# breakout.net
KiCad netlist of a schematic drawn in EAGLE
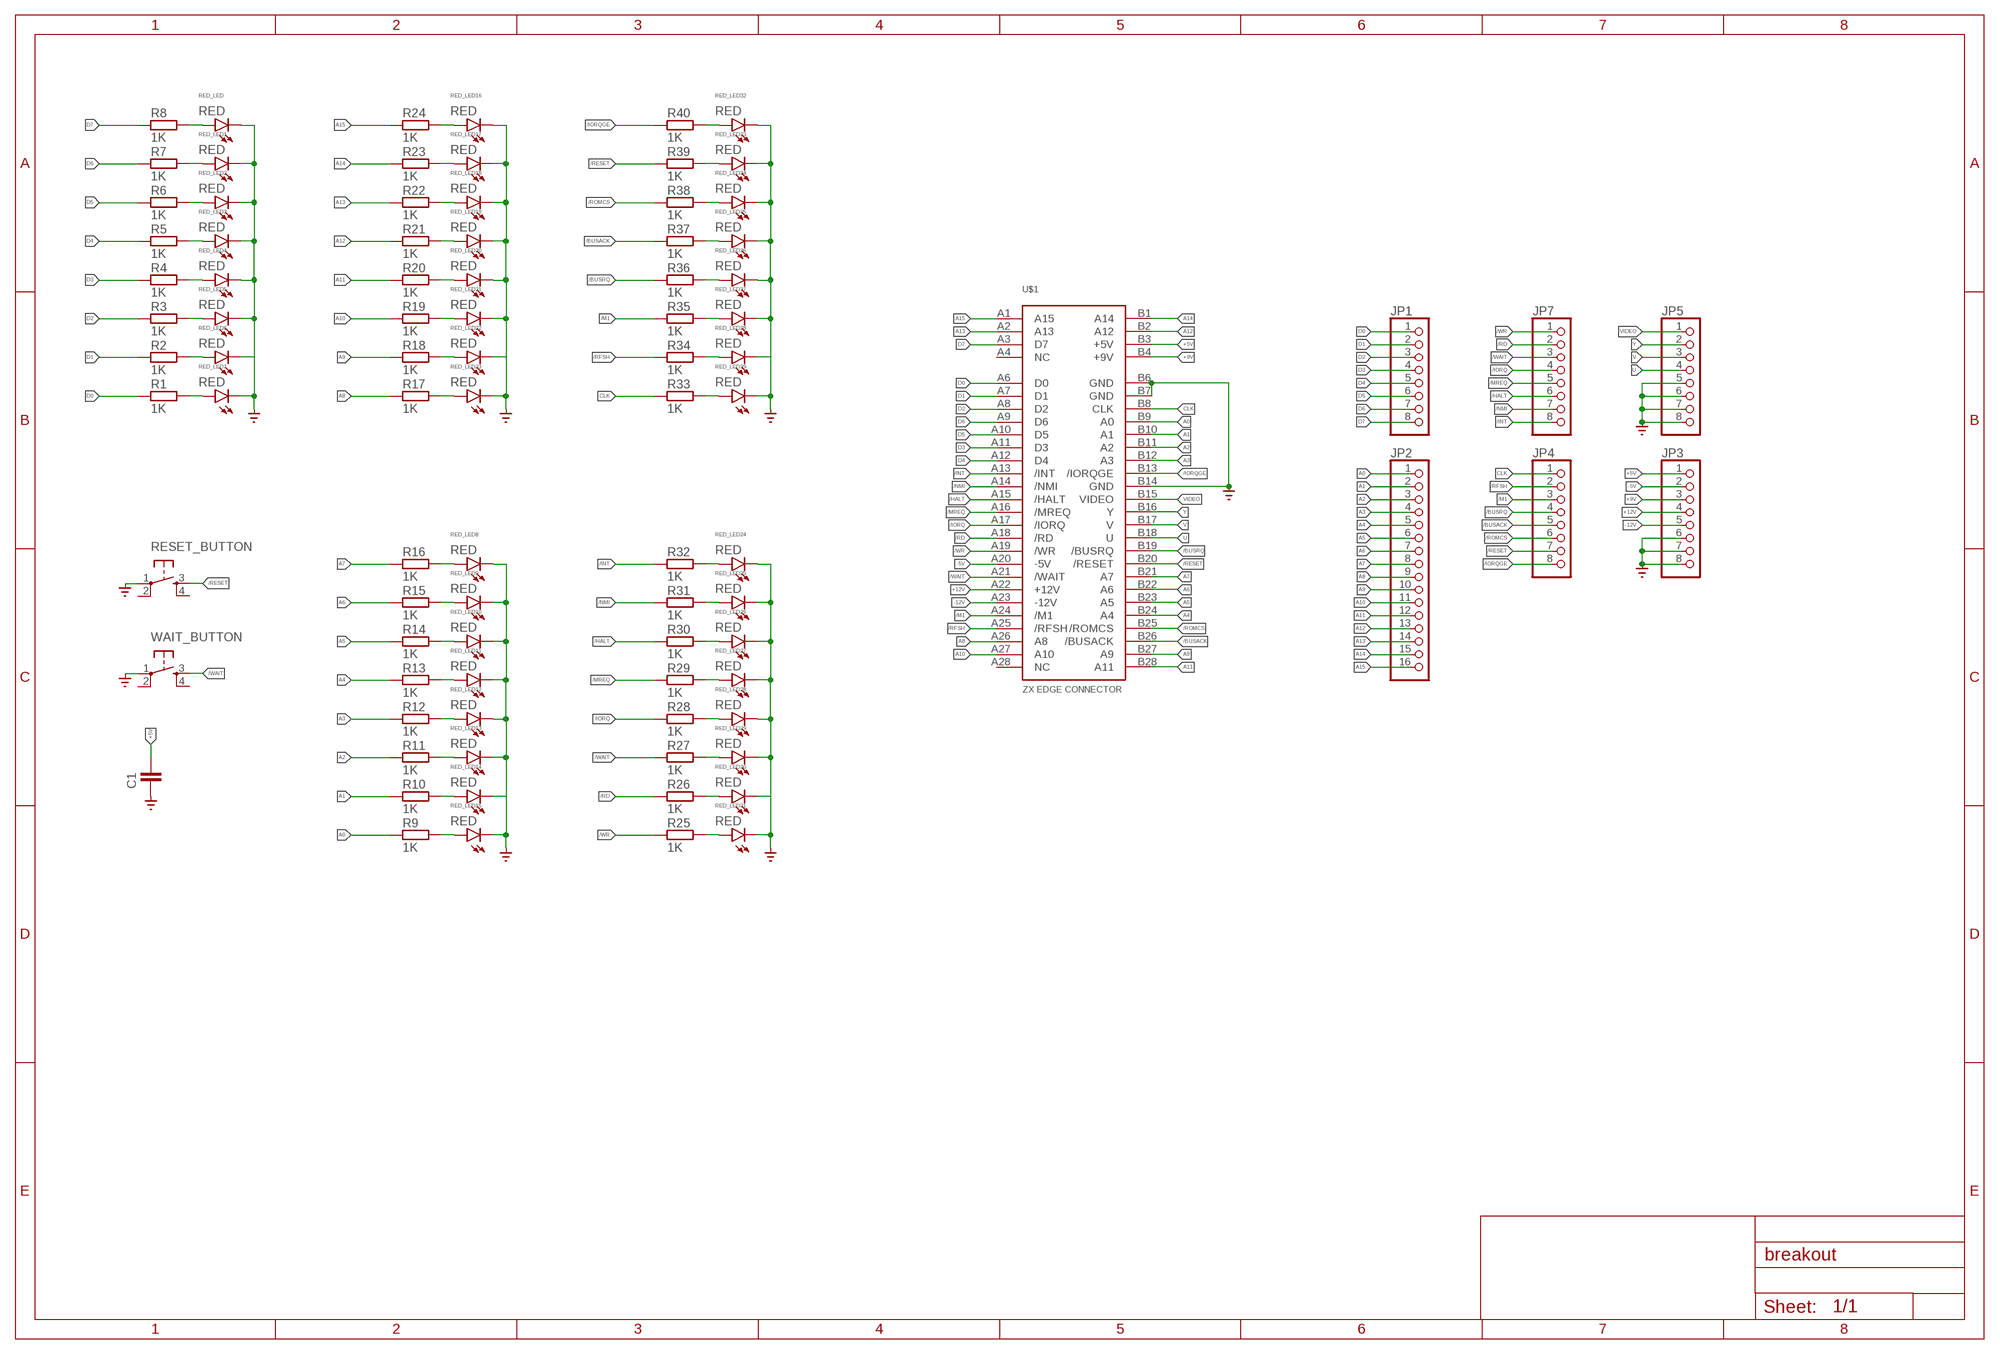
[diagram p0: schematic, sheet 1]

(export (version "E")
  (design (tool "Eeschema 10.0.6"))
  (components
    (comp (ref "C1")
      (value "1u")
      (footprint "eagle-import:C0402")
      (libsource (lib "eagle-import") (part "C-EUC0402"))
    )
    (comp (ref "JP1")
      (value "PINHD-1X8")
      (footprint "eagle-import:1X08")
      (libsource (lib "eagle-import") (part "PINHD-1X8"))
    )
    (comp (ref "JP2")
      (value "PINHD-1X16")
      (footprint "eagle-import:1X16")
      (libsource (lib "eagle-import") (part "PINHD-1X16"))
    )
    (comp (ref "JP3")
      (value "PINHD-1X8")
      (footprint "eagle-import:1X08")
      (libsource (lib "eagle-import") (part "PINHD-1X8"))
    )
    (comp (ref "JP4")
      (value "PINHD-1X8")
      (footprint "eagle-import:1X08")
      (libsource (lib "eagle-import") (part "PINHD-1X8"))
    )
    (comp (ref "JP5")
      (value "PINHD-1X8")
      (footprint "eagle-import:1X08")
      (libsource (lib "eagle-import") (part "PINHD-1X8"))
    )
    (comp (ref "JP7")
      (value "PINHD-1X8")
      (footprint "eagle-import:1X08")
      (libsource (lib "eagle-import") (part "PINHD-1X8"))
    )
    (comp (ref "R1")
      (value "1K")
      (footprint "eagle-import:R0402")
      (libsource (lib "eagle-import") (part "R-EU_R0402"))
    )
    (comp (ref "R2")
      (value "1K")
      (footprint "eagle-import:R0402")
      (libsource (lib "eagle-import") (part "R-EU_R0402"))
    )
    (comp (ref "R3")
      (value "1K")
      (footprint "eagle-import:R0402")
      (libsource (lib "eagle-import") (part "R-EU_R0402"))
    )
    (comp (ref "R4")
      (value "1K")
      (footprint "eagle-import:R0402")
      (libsource (lib "eagle-import") (part "R-EU_R0402"))
    )
    (comp (ref "R5")
      (value "1K")
      (footprint "eagle-import:R0402")
      (libsource (lib "eagle-import") (part "R-EU_R0402"))
    )
    (comp (ref "R6")
      (value "1K")
      (footprint "eagle-import:R0402")
      (libsource (lib "eagle-import") (part "R-EU_R0402"))
    )
    (comp (ref "R7")
      (value "1K")
      (footprint "eagle-import:R0402")
      (libsource (lib "eagle-import") (part "R-EU_R0402"))
    )
    (comp (ref "R8")
      (value "1K")
      (footprint "eagle-import:R0402")
      (libsource (lib "eagle-import") (part "R-EU_R0402"))
    )
    (comp (ref "R9")
      (value "1K")
      (footprint "eagle-import:R0402")
      (libsource (lib "eagle-import") (part "R-EU_R0402"))
    )
    (comp (ref "R10")
      (value "1K")
      (footprint "eagle-import:R0402")
      (libsource (lib "eagle-import") (part "R-EU_R0402"))
    )
    (comp (ref "R11")
      (value "1K")
      (footprint "eagle-import:R0402")
      (libsource (lib "eagle-import") (part "R-EU_R0402"))
    )
    (comp (ref "R12")
      (value "1K")
      (footprint "eagle-import:R0402")
      (libsource (lib "eagle-import") (part "R-EU_R0402"))
    )
    (comp (ref "R13")
      (value "1K")
      (footprint "eagle-import:R0402")
      (libsource (lib "eagle-import") (part "R-EU_R0402"))
    )
    (comp (ref "R14")
      (value "1K")
      (footprint "eagle-import:R0402")
      (libsource (lib "eagle-import") (part "R-EU_R0402"))
    )
    (comp (ref "R15")
      (value "1K")
      (footprint "eagle-import:R0402")
      (libsource (lib "eagle-import") (part "R-EU_R0402"))
    )
    (comp (ref "R16")
      (value "1K")
      (footprint "eagle-import:R0402")
      (libsource (lib "eagle-import") (part "R-EU_R0402"))
    )
    (comp (ref "R17")
      (value "1K")
      (footprint "eagle-import:R0402")
      (libsource (lib "eagle-import") (part "R-EU_R0402"))
    )
    (comp (ref "R18")
      (value "1K")
      (footprint "eagle-import:R0402")
      (libsource (lib "eagle-import") (part "R-EU_R0402"))
    )
    (comp (ref "R19")
      (value "1K")
      (footprint "eagle-import:R0402")
      (libsource (lib "eagle-import") (part "R-EU_R0402"))
    )
    (comp (ref "R20")
      (value "1K")
      (footprint "eagle-import:R0402")
      (libsource (lib "eagle-import") (part "R-EU_R0402"))
    )
    (comp (ref "R21")
      (value "1K")
      (footprint "eagle-import:R0402")
      (libsource (lib "eagle-import") (part "R-EU_R0402"))
    )
    (comp (ref "R22")
      (value "1K")
      (footprint "eagle-import:R0402")
      (libsource (lib "eagle-import") (part "R-EU_R0402"))
    )
    (comp (ref "R23")
      (value "1K")
      (footprint "eagle-import:R0402")
      (libsource (lib "eagle-import") (part "R-EU_R0402"))
    )
    (comp (ref "R24")
      (value "1K")
      (footprint "eagle-import:R0402")
      (libsource (lib "eagle-import") (part "R-EU_R0402"))
    )
    (comp (ref "R25")
      (value "1K")
      (footprint "eagle-import:R0402")
      (libsource (lib "eagle-import") (part "R-EU_R0402"))
    )
    (comp (ref "R26")
      (value "1K")
      (footprint "eagle-import:R0402")
      (libsource (lib "eagle-import") (part "R-EU_R0402"))
    )
    (comp (ref "R27")
      (value "1K")
      (footprint "eagle-import:R0402")
      (libsource (lib "eagle-import") (part "R-EU_R0402"))
    )
    (comp (ref "R28")
      (value "1K")
      (footprint "eagle-import:R0402")
      (libsource (lib "eagle-import") (part "R-EU_R0402"))
    )
    (comp (ref "R29")
      (value "1K")
      (footprint "eagle-import:R0402")
      (libsource (lib "eagle-import") (part "R-EU_R0402"))
    )
    (comp (ref "R30")
      (value "1K")
      (footprint "eagle-import:R0402")
      (libsource (lib "eagle-import") (part "R-EU_R0402"))
    )
    (comp (ref "R31")
      (value "1K")
      (footprint "eagle-import:R0402")
      (libsource (lib "eagle-import") (part "R-EU_R0402"))
    )
    (comp (ref "R32")
      (value "1K")
      (footprint "eagle-import:R0402")
      (libsource (lib "eagle-import") (part "R-EU_R0402"))
    )
    (comp (ref "R33")
      (value "1K")
      (footprint "eagle-import:R0402")
      (libsource (lib "eagle-import") (part "R-EU_R0402"))
    )
    (comp (ref "R34")
      (value "1K")
      (footprint "eagle-import:R0402")
      (libsource (lib "eagle-import") (part "R-EU_R0402"))
    )
    (comp (ref "R35")
      (value "1K")
      (footprint "eagle-import:R0402")
      (libsource (lib "eagle-import") (part "R-EU_R0402"))
    )
    (comp (ref "R36")
      (value "1K")
      (footprint "eagle-import:R0402")
      (libsource (lib "eagle-import") (part "R-EU_R0402"))
    )
    (comp (ref "R37")
      (value "1K")
      (footprint "eagle-import:R0402")
      (libsource (lib "eagle-import") (part "R-EU_R0402"))
    )
    (comp (ref "R38")
      (value "1K")
      (footprint "eagle-import:R0402")
      (libsource (lib "eagle-import") (part "R-EU_R0402"))
    )
    (comp (ref "R39")
      (value "1K")
      (footprint "eagle-import:R0402")
      (libsource (lib "eagle-import") (part "R-EU_R0402"))
    )
    (comp (ref "R40")
      (value "1K")
      (footprint "eagle-import:R0402")
      (libsource (lib "eagle-import") (part "R-EU_R0402"))
    )
    (comp (ref "RED_LED")
      (value "RED")
      (footprint "eagle-import:CHIPLED_0603")
      (libsource (lib "eagle-import") (part "LEDCHIPLED_0603"))
    )
    (comp (ref "RED_LED1")
      (value "RED")
      (footprint "eagle-import:CHIPLED_0603")
      (libsource (lib "eagle-import") (part "LEDCHIPLED_0603"))
    )
    (comp (ref "RED_LED2")
      (value "RED")
      (footprint "eagle-import:CHIPLED_0603")
      (libsource (lib "eagle-import") (part "LEDCHIPLED_0603"))
    )
    (comp (ref "RED_LED3")
      (value "RED")
      (footprint "eagle-import:CHIPLED_0603")
      (libsource (lib "eagle-import") (part "LEDCHIPLED_0603"))
    )
    (comp (ref "RED_LED4")
      (value "RED")
      (footprint "eagle-import:CHIPLED_0603")
      (libsource (lib "eagle-import") (part "LEDCHIPLED_0603"))
    )
    (comp (ref "RED_LED5")
      (value "RED")
      (footprint "eagle-import:CHIPLED_0603")
      (libsource (lib "eagle-import") (part "LEDCHIPLED_0603"))
    )
    (comp (ref "RED_LED6")
      (value "RED")
      (footprint "eagle-import:CHIPLED_0603")
      (libsource (lib "eagle-import") (part "LEDCHIPLED_0603"))
    )
    (comp (ref "RED_LED7")
      (value "RED")
      (footprint "eagle-import:CHIPLED_0603")
      (libsource (lib "eagle-import") (part "LEDCHIPLED_0603"))
    )
    (comp (ref "RED_LED8")
      (value "RED")
      (footprint "eagle-import:CHIPLED_0603")
      (libsource (lib "eagle-import") (part "LEDCHIPLED_0603"))
    )
    (comp (ref "RED_LED9")
      (value "RED")
      (footprint "eagle-import:CHIPLED_0603")
      (libsource (lib "eagle-import") (part "LEDCHIPLED_0603"))
    )
    (comp (ref "RED_LED10")
      (value "RED")
      (footprint "eagle-import:CHIPLED_0603")
      (libsource (lib "eagle-import") (part "LEDCHIPLED_0603"))
    )
    (comp (ref "RED_LED11")
      (value "RED")
      (footprint "eagle-import:CHIPLED_0603")
      (libsource (lib "eagle-import") (part "LEDCHIPLED_0603"))
    )
    (comp (ref "RED_LED12")
      (value "RED")
      (footprint "eagle-import:CHIPLED_0603")
      (libsource (lib "eagle-import") (part "LEDCHIPLED_0603"))
    )
    (comp (ref "RED_LED13")
      (value "RED")
      (footprint "eagle-import:CHIPLED_0603")
      (libsource (lib "eagle-import") (part "LEDCHIPLED_0603"))
    )
    (comp (ref "RED_LED14")
      (value "RED")
      (footprint "eagle-import:CHIPLED_0603")
      (libsource (lib "eagle-import") (part "LEDCHIPLED_0603"))
    )
    (comp (ref "RED_LED15")
      (value "RED")
      (footprint "eagle-import:CHIPLED_0603")
      (libsource (lib "eagle-import") (part "LEDCHIPLED_0603"))
    )
    (comp (ref "RED_LED16")
      (value "RED")
      (footprint "eagle-import:CHIPLED_0603")
      (libsource (lib "eagle-import") (part "LEDCHIPLED_0603"))
    )
    (comp (ref "RED_LED17")
      (value "RED")
      (footprint "eagle-import:CHIPLED_0603")
      (libsource (lib "eagle-import") (part "LEDCHIPLED_0603"))
    )
    (comp (ref "RED_LED18")
      (value "RED")
      (footprint "eagle-import:CHIPLED_0603")
      (libsource (lib "eagle-import") (part "LEDCHIPLED_0603"))
    )
    (comp (ref "RED_LED19")
      (value "RED")
      (footprint "eagle-import:CHIPLED_0603")
      (libsource (lib "eagle-import") (part "LEDCHIPLED_0603"))
    )
    (comp (ref "RED_LED20")
      (value "RED")
      (footprint "eagle-import:CHIPLED_0603")
      (libsource (lib "eagle-import") (part "LEDCHIPLED_0603"))
    )
    (comp (ref "RED_LED21")
      (value "RED")
      (footprint "eagle-import:CHIPLED_0603")
      (libsource (lib "eagle-import") (part "LEDCHIPLED_0603"))
    )
    (comp (ref "RED_LED22")
      (value "RED")
      (footprint "eagle-import:CHIPLED_0603")
      (libsource (lib "eagle-import") (part "LEDCHIPLED_0603"))
    )
    (comp (ref "RED_LED23")
      (value "RED")
      (footprint "eagle-import:CHIPLED_0603")
      (libsource (lib "eagle-import") (part "LEDCHIPLED_0603"))
    )
    (comp (ref "RED_LED24")
      (value "RED")
      (footprint "eagle-import:CHIPLED_0603")
      (libsource (lib "eagle-import") (part "LEDCHIPLED_0603"))
    )
    (comp (ref "RED_LED25")
      (value "RED")
      (footprint "eagle-import:CHIPLED_0603")
      (libsource (lib "eagle-import") (part "LEDCHIPLED_0603"))
    )
    (comp (ref "RED_LED26")
      (value "RED")
      (footprint "eagle-import:CHIPLED_0603")
      (libsource (lib "eagle-import") (part "LEDCHIPLED_0603"))
    )
    (comp (ref "RED_LED27")
      (value "RED")
      (footprint "eagle-import:CHIPLED_0603")
      (libsource (lib "eagle-import") (part "LEDCHIPLED_0603"))
    )
    (comp (ref "RED_LED28")
      (value "RED")
      (footprint "eagle-import:CHIPLED_0603")
      (libsource (lib "eagle-import") (part "LEDCHIPLED_0603"))
    )
    (comp (ref "RED_LED29")
      (value "RED")
      (footprint "eagle-import:CHIPLED_0603")
      (libsource (lib "eagle-import") (part "LEDCHIPLED_0603"))
    )
    (comp (ref "RED_LED30")
      (value "RED")
      (footprint "eagle-import:CHIPLED_0603")
      (libsource (lib "eagle-import") (part "LEDCHIPLED_0603"))
    )
    (comp (ref "RED_LED31")
      (value "RED")
      (footprint "eagle-import:CHIPLED_0603")
      (libsource (lib "eagle-import") (part "LEDCHIPLED_0603"))
    )
    (comp (ref "RED_LED32")
      (value "RED")
      (footprint "eagle-import:CHIPLED_0603")
      (libsource (lib "eagle-import") (part "LEDCHIPLED_0603"))
    )
    (comp (ref "RED_LED33")
      (value "RED")
      (footprint "eagle-import:CHIPLED_0603")
      (libsource (lib "eagle-import") (part "LEDCHIPLED_0603"))
    )
    (comp (ref "RED_LED34")
      (value "RED")
      (footprint "eagle-import:CHIPLED_0603")
      (libsource (lib "eagle-import") (part "LEDCHIPLED_0603"))
    )
    (comp (ref "RED_LED35")
      (value "RED")
      (footprint "eagle-import:CHIPLED_0603")
      (libsource (lib "eagle-import") (part "LEDCHIPLED_0603"))
    )
    (comp (ref "RED_LED36")
      (value "RED")
      (footprint "eagle-import:CHIPLED_0603")
      (libsource (lib "eagle-import") (part "LEDCHIPLED_0603"))
    )
    (comp (ref "RED_LED37")
      (value "RED")
      (footprint "eagle-import:CHIPLED_0603")
      (libsource (lib "eagle-import") (part "LEDCHIPLED_0603"))
    )
    (comp (ref "RED_LED38")
      (value "RED")
      (footprint "eagle-import:CHIPLED_0603")
      (libsource (lib "eagle-import") (part "LEDCHIPLED_0603"))
    )
    (comp (ref "RED_LED39")
      (value "RED")
      (footprint "eagle-import:CHIPLED_0603")
      (libsource (lib "eagle-import") (part "LEDCHIPLED_0603"))
    )
    (comp (ref "RESET_BUTTON")
      (value "10-XX")
      (footprint "eagle-import:B3F-10XX-3D")
      (libsource (lib "eagle-import") (part "10-XX"))
    )
    (comp (ref "U$1")
      (value "ZX-SPECTRUM-EDGE-CONNECTOR")
      (footprint "eagle-import:ZX-SPECTRUM-EDGE-CONNECTOR")
      (libsource (lib "eagle-import") (part "ZX-SPECTRUM-EDGE-CONNECTOR"))
    )
    (comp (ref "WAIT_BUTTON")
      (value "10-XX")
      (footprint "eagle-import:B3F-10XX-3D")
      (libsource (lib "eagle-import") (part "10-XX"))
    )
  )
  (nets
    (net (code "1") (name "+5V") (class "Default")
      (node (ref "C1") (pin "1") (pinfunction "1_1") (pintype "passive"))
      (node (ref "JP3") (pin "1") (pinfunction "1_1") (pintype "passive"))
      (node (ref "U$1") (pin "B3") (pinfunction "+5V_B3") (pintype "bidirectional"))
    )
    (net (code "2") (name "+9V") (class "Default")
      (node (ref "JP3") (pin "3") (pinfunction "3_3") (pintype "passive"))
      (node (ref "U$1") (pin "B4") (pinfunction "+9V_B4") (pintype "bidirectional"))
    )
    (net (code "3") (name "+12V") (class "Default")
      (node (ref "JP3") (pin "4") (pinfunction "4_4") (pintype "passive"))
      (node (ref "U$1") (pin "A22") (pinfunction "+12V_A22") (pintype "bidirectional"))
    )
    (net (code "4") (name "-5V") (class "Default")
      (node (ref "JP3") (pin "2") (pinfunction "2_2") (pintype "passive"))
      (node (ref "U$1") (pin "A20") (pinfunction "-5V_A20") (pintype "bidirectional"))
    )
    (net (code "5") (name "-12V") (class "Default")
      (node (ref "JP3") (pin "5") (pinfunction "5_5") (pintype "passive"))
      (node (ref "U$1") (pin "A23") (pinfunction "-12V_A23") (pintype "bidirectional"))
    )
    (net (code "6") (name "A0") (class "Default")
      (node (ref "JP2") (pin "1") (pinfunction "1_1") (pintype "passive"))
      (node (ref "R9") (pin "1") (pinfunction "1_1") (pintype "passive"))
      (node (ref "U$1") (pin "B9") (pinfunction "A0_B9") (pintype "bidirectional"))
    )
    (net (code "7") (name "A1") (class "Default")
      (node (ref "JP2") (pin "2") (pinfunction "2_2") (pintype "passive"))
      (node (ref "R10") (pin "1") (pinfunction "1_1") (pintype "passive"))
      (node (ref "U$1") (pin "B10") (pinfunction "A1_B10") (pintype "bidirectional"))
    )
    (net (code "8") (name "A2") (class "Default")
      (node (ref "JP2") (pin "3") (pinfunction "3_3") (pintype "passive"))
      (node (ref "R11") (pin "1") (pinfunction "1_1") (pintype "passive"))
      (node (ref "U$1") (pin "B11") (pinfunction "A2_B11") (pintype "bidirectional"))
    )
    (net (code "9") (name "A3") (class "Default")
      (node (ref "JP2") (pin "4") (pinfunction "4_4") (pintype "passive"))
      (node (ref "R12") (pin "1") (pinfunction "1_1") (pintype "passive"))
      (node (ref "U$1") (pin "B12") (pinfunction "A3_B12") (pintype "bidirectional"))
    )
    (net (code "10") (name "A4") (class "Default")
      (node (ref "JP2") (pin "5") (pinfunction "5_5") (pintype "passive"))
      (node (ref "R13") (pin "1") (pinfunction "1_1") (pintype "passive"))
      (node (ref "U$1") (pin "B24") (pinfunction "A4_B24") (pintype "bidirectional"))
    )
    (net (code "11") (name "A5") (class "Default")
      (node (ref "JP2") (pin "6") (pinfunction "6_6") (pintype "passive"))
      (node (ref "R14") (pin "1") (pinfunction "1_1") (pintype "passive"))
      (node (ref "U$1") (pin "B23") (pinfunction "A5_B23") (pintype "bidirectional"))
    )
    (net (code "12") (name "A6") (class "Default")
      (node (ref "JP2") (pin "7") (pinfunction "7_7") (pintype "passive"))
      (node (ref "R15") (pin "1") (pinfunction "1_1") (pintype "passive"))
      (node (ref "U$1") (pin "B22") (pinfunction "A6_B22") (pintype "bidirectional"))
    )
    (net (code "13") (name "A7") (class "Default")
      (node (ref "JP2") (pin "8") (pinfunction "8_8") (pintype "passive"))
      (node (ref "R16") (pin "1") (pinfunction "1_1") (pintype "passive"))
      (node (ref "U$1") (pin "B21") (pinfunction "A7_B21") (pintype "bidirectional"))
    )
    (net (code "14") (name "A8") (class "Default")
      (node (ref "JP2") (pin "9") (pinfunction "9_9") (pintype "passive"))
      (node (ref "R17") (pin "1") (pinfunction "1_1") (pintype "passive"))
      (node (ref "U$1") (pin "A26") (pinfunction "A8_A26") (pintype "bidirectional"))
    )
    (net (code "15") (name "A9") (class "Default")
      (node (ref "JP2") (pin "10") (pinfunction "10_10") (pintype "passive"))
      (node (ref "R18") (pin "1") (pinfunction "1_1") (pintype "passive"))
      (node (ref "U$1") (pin "B27") (pinfunction "A9_B27") (pintype "bidirectional"))
    )
    (net (code "16") (name "A10") (class "Default")
      (node (ref "JP2") (pin "11") (pinfunction "11_11") (pintype "passive"))
      (node (ref "R19") (pin "1") (pinfunction "1_1") (pintype "passive"))
      (node (ref "U$1") (pin "A27") (pinfunction "A10_A27") (pintype "bidirectional"))
    )
    (net (code "17") (name "A11") (class "Default")
      (node (ref "JP2") (pin "12") (pinfunction "12_12") (pintype "passive"))
      (node (ref "R20") (pin "1") (pinfunction "1_1") (pintype "passive"))
      (node (ref "U$1") (pin "B28") (pinfunction "A11_B28") (pintype "bidirectional"))
    )
    (net (code "18") (name "A12") (class "Default")
      (node (ref "JP2") (pin "13") (pinfunction "13_13") (pintype "passive"))
      (node (ref "R21") (pin "1") (pinfunction "1_1") (pintype "passive"))
      (node (ref "U$1") (pin "B2") (pinfunction "A12_B2") (pintype "bidirectional"))
    )
    (net (code "19") (name "A13") (class "Default")
      (node (ref "JP2") (pin "14") (pinfunction "14_14") (pintype "passive"))
      (node (ref "R22") (pin "1") (pinfunction "1_1") (pintype "passive"))
      (node (ref "U$1") (pin "A2") (pinfunction "A13_A2") (pintype "bidirectional"))
    )
    (net (code "20") (name "A14") (class "Default")
      (node (ref "JP2") (pin "15") (pinfunction "15_15") (pintype "passive"))
      (node (ref "R23") (pin "1") (pinfunction "1_1") (pintype "passive"))
      (node (ref "U$1") (pin "B1") (pinfunction "A14_B1") (pintype "bidirectional"))
    )
    (net (code "21") (name "A15") (class "Default")
      (node (ref "JP2") (pin "16") (pinfunction "16_16") (pintype "passive"))
      (node (ref "R24") (pin "1") (pinfunction "1_1") (pintype "passive"))
      (node (ref "U$1") (pin "A1") (pinfunction "A15_A1") (pintype "bidirectional"))
    )
    (net (code "22") (name "CLK") (class "Default")
      (node (ref "JP4") (pin "1") (pinfunction "1_1") (pintype "passive"))
      (node (ref "R33") (pin "1") (pinfunction "1_1") (pintype "passive"))
      (node (ref "U$1") (pin "B8") (pinfunction "CLK_B8") (pintype "bidirectional"))
    )
    (net (code "23") (name "D0") (class "Default")
      (node (ref "JP1") (pin "1") (pinfunction "1_1") (pintype "passive"))
      (node (ref "R1") (pin "1") (pinfunction "1_1") (pintype "passive"))
      (node (ref "U$1") (pin "A6") (pinfunction "D0_A6") (pintype "bidirectional"))
    )
    (net (code "24") (name "D1") (class "Default")
      (node (ref "JP1") (pin "2") (pinfunction "2_2") (pintype "passive"))
      (node (ref "R2") (pin "1") (pinfunction "1_1") (pintype "passive"))
      (node (ref "U$1") (pin "A7") (pinfunction "D1_A7") (pintype "bidirectional"))
    )
    (net (code "25") (name "D2") (class "Default")
      (node (ref "JP1") (pin "3") (pinfunction "3_3") (pintype "passive"))
      (node (ref "R3") (pin "1") (pinfunction "1_1") (pintype "passive"))
      (node (ref "U$1") (pin "A8") (pinfunction "D2_A8") (pintype "bidirectional"))
    )
    (net (code "26") (name "D3") (class "Default")
      (node (ref "JP1") (pin "4") (pinfunction "4_4") (pintype "passive"))
      (node (ref "R4") (pin "1") (pinfunction "1_1") (pintype "passive"))
      (node (ref "U$1") (pin "A11") (pinfunction "D3_A11") (pintype "bidirectional"))
    )
    (net (code "27") (name "D4") (class "Default")
      (node (ref "JP1") (pin "5") (pinfunction "5_5") (pintype "passive"))
      (node (ref "R5") (pin "1") (pinfunction "1_1") (pintype "passive"))
      (node (ref "U$1") (pin "A12") (pinfunction "D4_A12") (pintype "bidirectional"))
    )
    (net (code "28") (name "D5") (class "Default")
      (node (ref "JP1") (pin "6") (pinfunction "6_6") (pintype "passive"))
      (node (ref "R6") (pin "1") (pinfunction "1_1") (pintype "passive"))
      (node (ref "U$1") (pin "A10") (pinfunction "D5_A10") (pintype "bidirectional"))
    )
    (net (code "29") (name "D6") (class "Default")
      (node (ref "JP1") (pin "7") (pinfunction "7_7") (pintype "passive"))
      (node (ref "R7") (pin "1") (pinfunction "1_1") (pintype "passive"))
      (node (ref "U$1") (pin "A9") (pinfunction "D6_A9") (pintype "bidirectional"))
    )
    (net (code "30") (name "D7") (class "Default")
      (node (ref "JP1") (pin "8") (pinfunction "8_8") (pintype "passive"))
      (node (ref "R8") (pin "1") (pinfunction "1_1") (pintype "passive"))
      (node (ref "U$1") (pin "A3") (pinfunction "D7_A3") (pintype "bidirectional"))
    )
    (net (code "31") (name "Net-(R1-Pad2)") (class "Default")
      (node (ref "R1") (pin "2") (pinfunction "2_2") (pintype "passive"))
      (node (ref "RED_LED7") (pin "A") (pinfunction "A_A") (pintype "passive"))
    )
    (net (code "32") (name "Net-(R2-Pad2)") (class "Default")
      (node (ref "R2") (pin "2") (pinfunction "2_2") (pintype "passive"))
      (node (ref "RED_LED6") (pin "A") (pinfunction "A_A") (pintype "passive"))
    )
    (net (code "33") (name "Net-(R3-Pad2)") (class "Default")
      (node (ref "R3") (pin "2") (pinfunction "2_2") (pintype "passive"))
      (node (ref "RED_LED5") (pin "A") (pinfunction "A_A") (pintype "passive"))
    )
    (net (code "34") (name "Net-(R4-Pad2)") (class "Default")
      (node (ref "R4") (pin "2") (pinfunction "2_2") (pintype "passive"))
      (node (ref "RED_LED4") (pin "A") (pinfunction "A_A") (pintype "passive"))
    )
    (net (code "35") (name "Net-(R5-Pad2)") (class "Default")
      (node (ref "R5") (pin "2") (pinfunction "2_2") (pintype "passive"))
      (node (ref "RED_LED3") (pin "A") (pinfunction "A_A") (pintype "passive"))
    )
    (net (code "36") (name "Net-(R6-Pad2)") (class "Default")
      (node (ref "R6") (pin "2") (pinfunction "2_2") (pintype "passive"))
      (node (ref "RED_LED2") (pin "A") (pinfunction "A_A") (pintype "passive"))
    )
    (net (code "37") (name "Net-(R7-Pad2)") (class "Default")
      (node (ref "R7") (pin "2") (pinfunction "2_2") (pintype "passive"))
      (node (ref "RED_LED1") (pin "A") (pinfunction "A_A") (pintype "passive"))
    )
    (net (code "38") (name "Net-(R8-Pad2)") (class "Default")
      (node (ref "R8") (pin "2") (pinfunction "2_2") (pintype "passive"))
      (node (ref "RED_LED") (pin "A") (pinfunction "A_A") (pintype "passive"))
    )
    (net (code "39") (name "Net-(R9-Pad2)") (class "Default")
      (node (ref "R9") (pin "2") (pinfunction "2_2") (pintype "passive"))
      (node (ref "RED_LED15") (pin "A") (pinfunction "A_A") (pintype "passive"))
    )
    (net (code "40") (name "Net-(R10-Pad2)") (class "Default")
      (node (ref "R10") (pin "2") (pinfunction "2_2") (pintype "passive"))
      (node (ref "RED_LED14") (pin "A") (pinfunction "A_A") (pintype "passive"))
    )
    (net (code "41") (name "Net-(R11-Pad2)") (class "Default")
      (node (ref "R11") (pin "2") (pinfunction "2_2") (pintype "passive"))
      (node (ref "RED_LED13") (pin "A") (pinfunction "A_A") (pintype "passive"))
    )
    (net (code "42") (name "Net-(R12-Pad2)") (class "Default")
      (node (ref "R12") (pin "2") (pinfunction "2_2") (pintype "passive"))
      (node (ref "RED_LED12") (pin "A") (pinfunction "A_A") (pintype "passive"))
    )
    (net (code "43") (name "Net-(R13-Pad2)") (class "Default")
      (node (ref "R13") (pin "2") (pinfunction "2_2") (pintype "passive"))
      (node (ref "RED_LED11") (pin "A") (pinfunction "A_A") (pintype "passive"))
    )
    (net (code "44") (name "Net-(R14-Pad2)") (class "Default")
      (node (ref "R14") (pin "2") (pinfunction "2_2") (pintype "passive"))
      (node (ref "RED_LED10") (pin "A") (pinfunction "A_A") (pintype "passive"))
    )
    (net (code "45") (name "Net-(R15-Pad2)") (class "Default")
      (node (ref "R15") (pin "2") (pinfunction "2_2") (pintype "passive"))
      (node (ref "RED_LED9") (pin "A") (pinfunction "A_A") (pintype "passive"))
    )
    (net (code "46") (name "Net-(R16-Pad2)") (class "Default")
      (node (ref "R16") (pin "2") (pinfunction "2_2") (pintype "passive"))
      (node (ref "RED_LED8") (pin "A") (pinfunction "A_A") (pintype "passive"))
    )
    (net (code "47") (name "Net-(R17-Pad2)") (class "Default")
      (node (ref "R17") (pin "2") (pinfunction "2_2") (pintype "passive"))
      (node (ref "RED_LED23") (pin "A") (pinfunction "A_A") (pintype "passive"))
    )
    (net (code "48") (name "Net-(R18-Pad2)") (class "Default")
      (node (ref "R18") (pin "2") (pinfunction "2_2") (pintype "passive"))
      (node (ref "RED_LED22") (pin "A") (pinfunction "A_A") (pintype "passive"))
    )
    (net (code "49") (name "Net-(R19-Pad2)") (class "Default")
      (node (ref "R19") (pin "2") (pinfunction "2_2") (pintype "passive"))
      (node (ref "RED_LED21") (pin "A") (pinfunction "A_A") (pintype "passive"))
    )
    (net (code "50") (name "Net-(R20-Pad2)") (class "Default")
      (node (ref "R20") (pin "2") (pinfunction "2_2") (pintype "passive"))
      (node (ref "RED_LED20") (pin "A") (pinfunction "A_A") (pintype "passive"))
    )
    (net (code "51") (name "Net-(R21-Pad2)") (class "Default")
      (node (ref "R21") (pin "2") (pinfunction "2_2") (pintype "passive"))
      (node (ref "RED_LED19") (pin "A") (pinfunction "A_A") (pintype "passive"))
    )
    (net (code "52") (name "Net-(R22-Pad2)") (class "Default")
      (node (ref "R22") (pin "2") (pinfunction "2_2") (pintype "passive"))
      (node (ref "RED_LED18") (pin "A") (pinfunction "A_A") (pintype "passive"))
    )
    (net (code "53") (name "Net-(R23-Pad2)") (class "Default")
      (node (ref "R23") (pin "2") (pinfunction "2_2") (pintype "passive"))
      (node (ref "RED_LED17") (pin "A") (pinfunction "A_A") (pintype "passive"))
    )
    (net (code "54") (name "Net-(R24-Pad2)") (class "Default")
      (node (ref "R24") (pin "2") (pinfunction "2_2") (pintype "passive"))
      (node (ref "RED_LED16") (pin "A") (pinfunction "A_A") (pintype "passive"))
    )
    (net (code "55") (name "Net-(R25-Pad2)") (class "Default")
      (node (ref "R25") (pin "2") (pinfunction "2_2") (pintype "passive"))
      (node (ref "RED_LED31") (pin "A") (pinfunction "A_A") (pintype "passive"))
    )
    (net (code "56") (name "Net-(R26-Pad2)") (class "Default")
      (node (ref "R26") (pin "2") (pinfunction "2_2") (pintype "passive"))
      (node (ref "RED_LED30") (pin "A") (pinfunction "A_A") (pintype "passive"))
    )
    (net (code "57") (name "Net-(R27-Pad2)") (class "Default")
      (node (ref "R27") (pin "2") (pinfunction "2_2") (pintype "passive"))
      (node (ref "RED_LED29") (pin "A") (pinfunction "A_A") (pintype "passive"))
    )
    (net (code "58") (name "Net-(R28-Pad2)") (class "Default")
      (node (ref "R28") (pin "2") (pinfunction "2_2") (pintype "passive"))
      (node (ref "RED_LED28") (pin "A") (pinfunction "A_A") (pintype "passive"))
    )
    (net (code "59") (name "Net-(R29-Pad2)") (class "Default")
      (node (ref "R29") (pin "2") (pinfunction "2_2") (pintype "passive"))
      (node (ref "RED_LED27") (pin "A") (pinfunction "A_A") (pintype "passive"))
    )
    (net (code "60") (name "Net-(R30-Pad2)") (class "Default")
      (node (ref "R30") (pin "2") (pinfunction "2_2") (pintype "passive"))
      (node (ref "RED_LED26") (pin "A") (pinfunction "A_A") (pintype "passive"))
    )
    (net (code "61") (name "Net-(R31-Pad2)") (class "Default")
      (node (ref "R31") (pin "2") (pinfunction "2_2") (pintype "passive"))
      (node (ref "RED_LED25") (pin "A") (pinfunction "A_A") (pintype "passive"))
    )
    (net (code "62") (name "Net-(R32-Pad2)") (class "Default")
      (node (ref "R32") (pin "2") (pinfunction "2_2") (pintype "passive"))
      (node (ref "RED_LED24") (pin "A") (pinfunction "A_A") (pintype "passive"))
    )
    (net (code "63") (name "Net-(R33-Pad2)") (class "Default")
      (node (ref "R33") (pin "2") (pinfunction "2_2") (pintype "passive"))
      (node (ref "RED_LED39") (pin "A") (pinfunction "A_A") (pintype "passive"))
    )
    (net (code "64") (name "Net-(R34-Pad2)") (class "Default")
      (node (ref "R34") (pin "2") (pinfunction "2_2") (pintype "passive"))
      (node (ref "RED_LED38") (pin "A") (pinfunction "A_A") (pintype "passive"))
    )
    (net (code "65") (name "Net-(R35-Pad2)") (class "Default")
      (node (ref "R35") (pin "2") (pinfunction "2_2") (pintype "passive"))
      (node (ref "RED_LED37") (pin "A") (pinfunction "A_A") (pintype "passive"))
    )
    (net (code "66") (name "Net-(R36-Pad2)") (class "Default")
      (node (ref "R36") (pin "2") (pinfunction "2_2") (pintype "passive"))
      (node (ref "RED_LED36") (pin "A") (pinfunction "A_A") (pintype "passive"))
    )
    (net (code "67") (name "Net-(R37-Pad2)") (class "Default")
      (node (ref "R37") (pin "2") (pinfunction "2_2") (pintype "passive"))
      (node (ref "RED_LED35") (pin "A") (pinfunction "A_A") (pintype "passive"))
    )
    (net (code "68") (name "Net-(R38-Pad2)") (class "Default")
      (node (ref "R38") (pin "2") (pinfunction "2_2") (pintype "passive"))
      (node (ref "RED_LED34") (pin "A") (pinfunction "A_A") (pintype "passive"))
    )
    (net (code "69") (name "Net-(R39-Pad2)") (class "Default")
      (node (ref "R39") (pin "2") (pinfunction "2_2") (pintype "passive"))
      (node (ref "RED_LED33") (pin "A") (pinfunction "A_A") (pintype "passive"))
    )
    (net (code "70") (name "Net-(R40-Pad2)") (class "Default")
      (node (ref "R40") (pin "2") (pinfunction "2_2") (pintype "passive"))
      (node (ref "RED_LED32") (pin "A") (pinfunction "A_A") (pintype "passive"))
    )
    (net (code "71") (name "SUPPLY0_GND_") (class "Default")
      (node (ref "C1") (pin "2") (pinfunction "2_2") (pintype "passive"))
      (node (ref "JP3") (pin "6") (pinfunction "6_6") (pintype "passive"))
      (node (ref "JP3") (pin "7") (pinfunction "7_7") (pintype "passive"))
      (node (ref "JP3") (pin "8") (pinfunction "8_8") (pintype "passive"))
      (node (ref "JP5") (pin "5") (pinfunction "5_5") (pintype "passive"))
      (node (ref "JP5") (pin "6") (pinfunction "6_6") (pintype "passive"))
      (node (ref "JP5") (pin "7") (pinfunction "7_7") (pintype "passive"))
      (node (ref "JP5") (pin "8") (pinfunction "8_8") (pintype "passive"))
      (node (ref "RED_LED") (pin "C") (pinfunction "C_C") (pintype "passive"))
      (node (ref "RED_LED1") (pin "C") (pinfunction "C_C") (pintype "passive"))
      (node (ref "RED_LED10") (pin "C") (pinfunction "C_C") (pintype "passive"))
      (node (ref "RED_LED11") (pin "C") (pinfunction "C_C") (pintype "passive"))
      (node (ref "RED_LED12") (pin "C") (pinfunction "C_C") (pintype "passive"))
      (node (ref "RED_LED13") (pin "C") (pinfunction "C_C") (pintype "passive"))
      (node (ref "RED_LED14") (pin "C") (pinfunction "C_C") (pintype "passive"))
      (node (ref "RED_LED15") (pin "C") (pinfunction "C_C") (pintype "passive"))
      (node (ref "RED_LED16") (pin "C") (pinfunction "C_C") (pintype "passive"))
      (node (ref "RED_LED17") (pin "C") (pinfunction "C_C") (pintype "passive"))
      (node (ref "RED_LED18") (pin "C") (pinfunction "C_C") (pintype "passive"))
      (node (ref "RED_LED19") (pin "C") (pinfunction "C_C") (pintype "passive"))
      (node (ref "RED_LED2") (pin "C") (pinfunction "C_C") (pintype "passive"))
      (node (ref "RED_LED20") (pin "C") (pinfunction "C_C") (pintype "passive"))
      (node (ref "RED_LED21") (pin "C") (pinfunction "C_C") (pintype "passive"))
      (node (ref "RED_LED22") (pin "C") (pinfunction "C_C") (pintype "passive"))
      (node (ref "RED_LED23") (pin "C") (pinfunction "C_C") (pintype "passive"))
      (node (ref "RED_LED24") (pin "C") (pinfunction "C_C") (pintype "passive"))
      (node (ref "RED_LED25") (pin "C") (pinfunction "C_C") (pintype "passive"))
      (node (ref "RED_LED26") (pin "C") (pinfunction "C_C") (pintype "passive"))
      (node (ref "RED_LED27") (pin "C") (pinfunction "C_C") (pintype "passive"))
      (node (ref "RED_LED28") (pin "C") (pinfunction "C_C") (pintype "passive"))
      (node (ref "RED_LED29") (pin "C") (pinfunction "C_C") (pintype "passive"))
      (node (ref "RED_LED3") (pin "C") (pinfunction "C_C") (pintype "passive"))
      (node (ref "RED_LED30") (pin "C") (pinfunction "C_C") (pintype "passive"))
      (node (ref "RED_LED31") (pin "C") (pinfunction "C_C") (pintype "passive"))
      (node (ref "RED_LED32") (pin "C") (pinfunction "C_C") (pintype "passive"))
      (node (ref "RED_LED33") (pin "C") (pinfunction "C_C") (pintype "passive"))
      (node (ref "RED_LED34") (pin "C") (pinfunction "C_C") (pintype "passive"))
      (node (ref "RED_LED35") (pin "C") (pinfunction "C_C") (pintype "passive"))
      (node (ref "RED_LED36") (pin "C") (pinfunction "C_C") (pintype "passive"))
      (node (ref "RED_LED37") (pin "C") (pinfunction "C_C") (pintype "passive"))
      (node (ref "RED_LED38") (pin "C") (pinfunction "C_C") (pintype "passive"))
      (node (ref "RED_LED39") (pin "C") (pinfunction "C_C") (pintype "passive"))
      (node (ref "RED_LED4") (pin "C") (pinfunction "C_C") (pintype "passive"))
      (node (ref "RED_LED5") (pin "C") (pinfunction "C_C") (pintype "passive"))
      (node (ref "RED_LED6") (pin "C") (pinfunction "C_C") (pintype "passive"))
      (node (ref "RED_LED7") (pin "C") (pinfunction "C_C") (pintype "passive"))
      (node (ref "RED_LED8") (pin "C") (pinfunction "C_C") (pintype "passive"))
      (node (ref "RED_LED9") (pin "C") (pinfunction "C_C") (pintype "passive"))
      (node (ref "RESET_BUTTON") (pin "1") (pinfunction "P_1") (pintype "passive"))
      (node (ref "U$1") (pin "B14") (pinfunction "GND_B14") (pintype "bidirectional"))
      (node (ref "U$1") (pin "B6") (pinfunction "GND_B6") (pintype "bidirectional"))
      (node (ref "U$1") (pin "B7") (pinfunction "GND_B7") (pintype "bidirectional"))
      (node (ref "WAIT_BUTTON") (pin "1") (pinfunction "P_1") (pintype "passive"))
    )
    (net (code "72") (name "U") (class "Default")
      (node (ref "JP5") (pin "4") (pinfunction "4_4") (pintype "passive"))
      (node (ref "U$1") (pin "B18") (pinfunction "U_B18") (pintype "bidirectional"))
    )
    (net (code "73") (name "V") (class "Default")
      (node (ref "JP5") (pin "3") (pinfunction "3_3") (pintype "passive"))
      (node (ref "U$1") (pin "B17") (pinfunction "V_B17") (pintype "bidirectional"))
    )
    (net (code "74") (name "VIDEO") (class "Default")
      (node (ref "JP5") (pin "1") (pinfunction "1_1") (pintype "passive"))
      (node (ref "U$1") (pin "B15") (pinfunction "VIDEO_B15") (pintype "bidirectional"))
    )
    (net (code "75") (name "Y") (class "Default")
      (node (ref "JP5") (pin "2") (pinfunction "2_2") (pintype "passive"))
      (node (ref "U$1") (pin "B16") (pinfunction "Y_B16") (pintype "bidirectional"))
    )
    (net (code "76") (name "unconnected-(RESET_BUTTON-P1-Pad2)") (class "Default")
      (node (ref "RESET_BUTTON") (pin "2") (pinfunction "P1_2") (pintype "passive"))
    )
    (net (code "77") (name "unconnected-(RESET_BUTTON-S1-Pad4)") (class "Default")
      (node (ref "RESET_BUTTON") (pin "4") (pinfunction "S1_4") (pintype "passive"))
    )
    (net (code "78") (name "unconnected-(U$1-NC-PadA4)") (class "Default")
      (node (ref "U$1") (pin "A4") (pinfunction "NC_A4") (pintype "no_connect"))
    )
    (net (code "79") (name "unconnected-(U$1-NC-PadA28)") (class "Default")
      (node (ref "U$1") (pin "A28") (pinfunction "NC_A28") (pintype "no_connect"))
    )
    (net (code "80") (name "unconnected-(WAIT_BUTTON-P1-Pad2)") (class "Default")
      (node (ref "WAIT_BUTTON") (pin "2") (pinfunction "P1_2") (pintype "passive"))
    )
    (net (code "81") (name "unconnected-(WAIT_BUTTON-S1-Pad4)") (class "Default")
      (node (ref "WAIT_BUTTON") (pin "4") (pinfunction "S1_4") (pintype "passive"))
    )
    (net (code "82") (name "{slash}BUSACK") (class "Default")
      (node (ref "JP4") (pin "5") (pinfunction "5_5") (pintype "passive"))
      (node (ref "R37") (pin "1") (pinfunction "1_1") (pintype "passive"))
      (node (ref "U$1") (pin "B26") (pinfunction "/BUSACK_B26") (pintype "bidirectional"))
    )
    (net (code "83") (name "{slash}BUSRQ") (class "Default")
      (node (ref "JP4") (pin "4") (pinfunction "4_4") (pintype "passive"))
      (node (ref "R36") (pin "1") (pinfunction "1_1") (pintype "passive"))
      (node (ref "U$1") (pin "B19") (pinfunction "/BUSRQ_B19") (pintype "bidirectional"))
    )
    (net (code "84") (name "{slash}HALT") (class "Default")
      (node (ref "JP7") (pin "6") (pinfunction "6_6") (pintype "passive"))
      (node (ref "R30") (pin "1") (pinfunction "1_1") (pintype "passive"))
      (node (ref "U$1") (pin "A15") (pinfunction "/HALT_A15") (pintype "bidirectional"))
    )
    (net (code "85") (name "{slash}INT") (class "Default")
      (node (ref "JP7") (pin "8") (pinfunction "8_8") (pintype "passive"))
      (node (ref "R32") (pin "1") (pinfunction "1_1") (pintype "passive"))
      (node (ref "U$1") (pin "A13") (pinfunction "/INT_A13") (pintype "bidirectional"))
    )
    (net (code "86") (name "{slash}IORQ") (class "Default")
      (node (ref "JP7") (pin "4") (pinfunction "4_4") (pintype "passive"))
      (node (ref "R28") (pin "1") (pinfunction "1_1") (pintype "passive"))
      (node (ref "U$1") (pin "A17") (pinfunction "/IORQ_A17") (pintype "bidirectional"))
    )
    (net (code "87") (name "{slash}IORQGE") (class "Default")
      (node (ref "JP4") (pin "8") (pinfunction "8_8") (pintype "passive"))
      (node (ref "R40") (pin "1") (pinfunction "1_1") (pintype "passive"))
      (node (ref "U$1") (pin "B13") (pinfunction "/IORQGE_B13") (pintype "bidirectional"))
    )
    (net (code "88") (name "{slash}M1") (class "Default")
      (node (ref "JP4") (pin "3") (pinfunction "3_3") (pintype "passive"))
      (node (ref "R35") (pin "1") (pinfunction "1_1") (pintype "passive"))
      (node (ref "U$1") (pin "A24") (pinfunction "/M1_A24") (pintype "bidirectional"))
    )
    (net (code "89") (name "{slash}MREQ") (class "Default")
      (node (ref "JP7") (pin "5") (pinfunction "5_5") (pintype "passive"))
      (node (ref "R29") (pin "1") (pinfunction "1_1") (pintype "passive"))
      (node (ref "U$1") (pin "A16") (pinfunction "/MREQ_A16") (pintype "bidirectional"))
    )
    (net (code "90") (name "{slash}NMI") (class "Default")
      (node (ref "JP7") (pin "7") (pinfunction "7_7") (pintype "passive"))
      (node (ref "R31") (pin "1") (pinfunction "1_1") (pintype "passive"))
      (node (ref "U$1") (pin "A14") (pinfunction "/NMI_A14") (pintype "bidirectional"))
    )
    (net (code "91") (name "{slash}RD") (class "Default")
      (node (ref "JP7") (pin "2") (pinfunction "2_2") (pintype "passive"))
      (node (ref "R26") (pin "1") (pinfunction "1_1") (pintype "passive"))
      (node (ref "U$1") (pin "A18") (pinfunction "/RD_A18") (pintype "bidirectional"))
    )
    (net (code "92") (name "{slash}RESET") (class "Default")
      (node (ref "JP4") (pin "7") (pinfunction "7_7") (pintype "passive"))
      (node (ref "R39") (pin "1") (pinfunction "1_1") (pintype "passive"))
      (node (ref "RESET_BUTTON") (pin "3") (pinfunction "S_3") (pintype "passive"))
      (node (ref "U$1") (pin "B20") (pinfunction "/RESET_B20") (pintype "bidirectional"))
    )
    (net (code "93") (name "{slash}RFSH") (class "Default")
      (node (ref "JP4") (pin "2") (pinfunction "2_2") (pintype "passive"))
      (node (ref "R34") (pin "1") (pinfunction "1_1") (pintype "passive"))
      (node (ref "U$1") (pin "A25") (pinfunction "/RFSH_A25") (pintype "bidirectional"))
    )
    (net (code "94") (name "{slash}ROMCS") (class "Default")
      (node (ref "JP4") (pin "6") (pinfunction "6_6") (pintype "passive"))
      (node (ref "R38") (pin "1") (pinfunction "1_1") (pintype "passive"))
      (node (ref "U$1") (pin "B25") (pinfunction "/ROMCS_B25") (pintype "bidirectional"))
    )
    (net (code "95") (name "{slash}WAIT") (class "Default")
      (node (ref "JP7") (pin "3") (pinfunction "3_3") (pintype "passive"))
      (node (ref "R27") (pin "1") (pinfunction "1_1") (pintype "passive"))
      (node (ref "U$1") (pin "A21") (pinfunction "/WAIT_A21") (pintype "bidirectional"))
      (node (ref "WAIT_BUTTON") (pin "3") (pinfunction "S_3") (pintype "passive"))
    )
    (net (code "96") (name "{slash}WR") (class "Default")
      (node (ref "JP7") (pin "1") (pinfunction "1_1") (pintype "passive"))
      (node (ref "R25") (pin "1") (pinfunction "1_1") (pintype "passive"))
      (node (ref "U$1") (pin "A19") (pinfunction "/WR_A19") (pintype "bidirectional"))
    )
  )
)
